# Drivers_-_Low_Current.net
KiCad netlist of a schematic drawn in Altium Designer
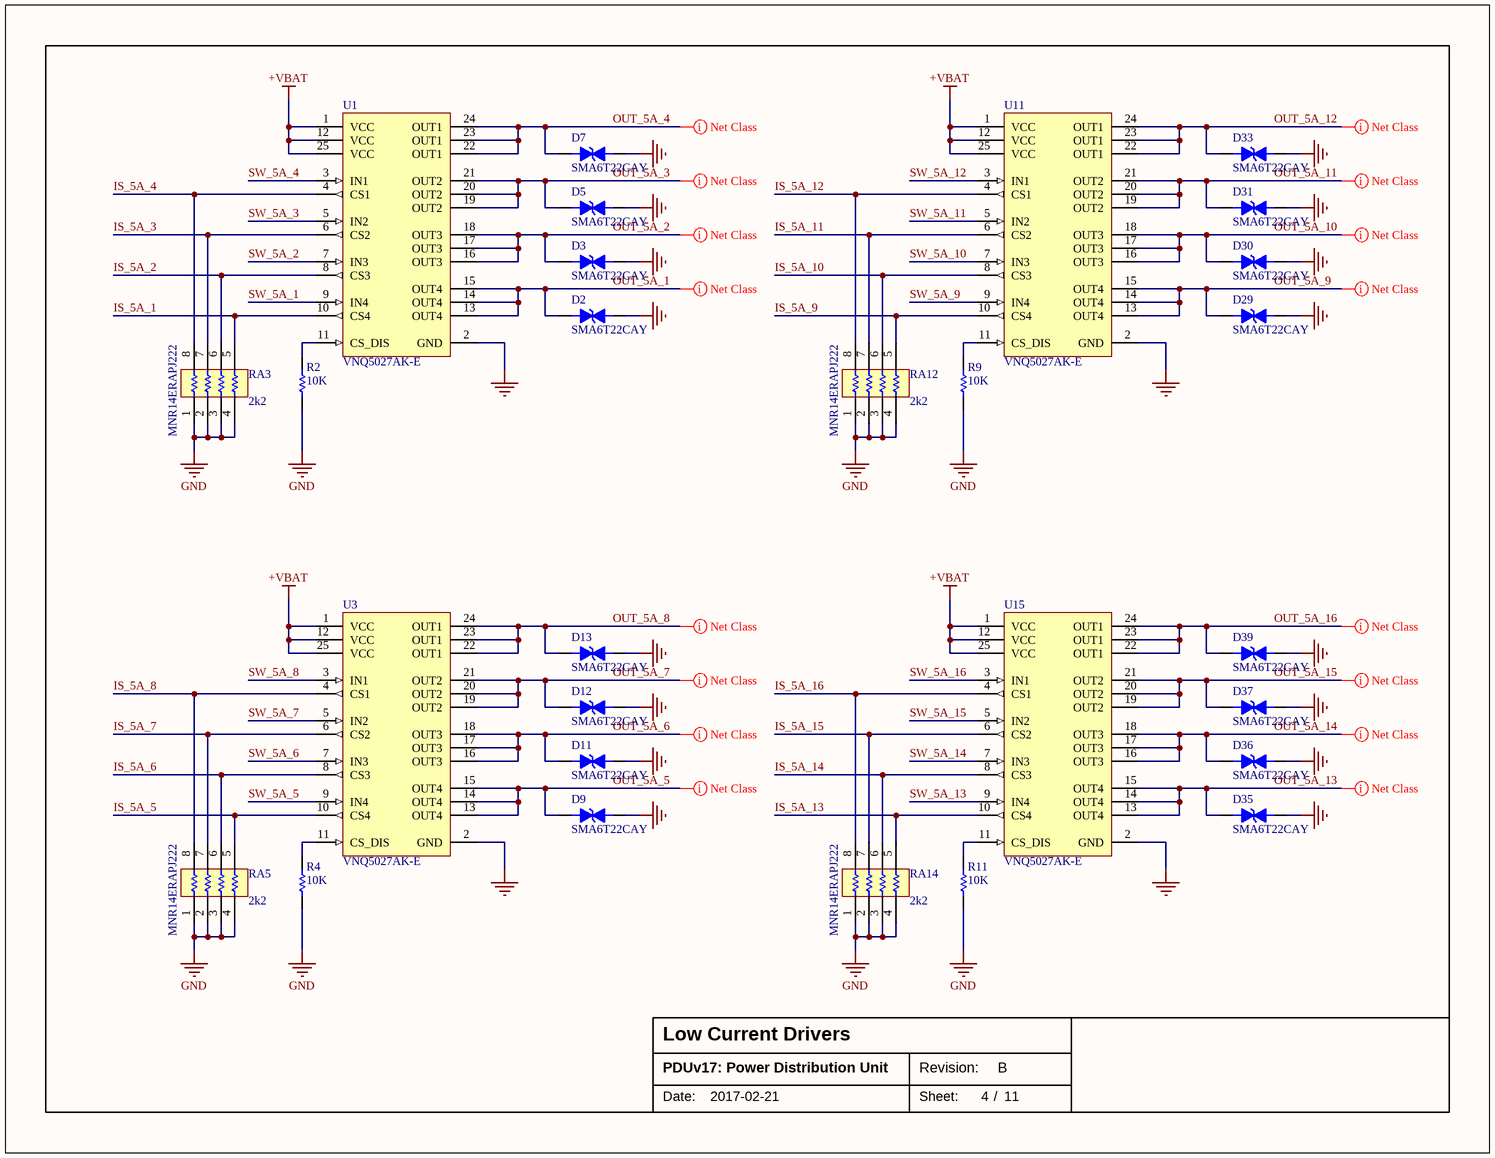
[diagram p0: Drivers - Low Current.SchDoc]

(export (version "E")
  (design (tool "Eeschema 10.0.6"))
  (components
    (comp (ref "D2")
      (value "SMA6T22CAY")
      (footprint "DIOM4326X25N")
      (libsource (lib "PDU-UV17") (part "SMA6T22CAY"))
    )
    (comp (ref "D3")
      (value "SMA6T22CAY")
      (footprint "DIOM4326X25N")
      (libsource (lib "PDU-UV17") (part "SMA6T22CAY"))
    )
    (comp (ref "D5")
      (value "SMA6T22CAY")
      (footprint "DIOM4326X25N")
      (libsource (lib "PDU-UV17") (part "SMA6T22CAY"))
    )
    (comp (ref "D7")
      (value "SMA6T22CAY")
      (footprint "DIOM4326X25N")
      (libsource (lib "PDU-UV17") (part "SMA6T22CAY"))
    )
    (comp (ref "D9")
      (value "SMA6T22CAY")
      (footprint "DIOM4326X25N")
      (libsource (lib "PDU-UV17") (part "SMA6T22CAY"))
    )
    (comp (ref "D11")
      (value "SMA6T22CAY")
      (footprint "DIOM4326X25N")
      (libsource (lib "PDU-UV17") (part "SMA6T22CAY"))
    )
    (comp (ref "D12")
      (value "SMA6T22CAY")
      (footprint "DIOM4326X25N")
      (libsource (lib "PDU-UV17") (part "SMA6T22CAY"))
    )
    (comp (ref "D13")
      (value "SMA6T22CAY")
      (footprint "DIOM4326X25N")
      (libsource (lib "PDU-UV17") (part "SMA6T22CAY"))
    )
    (comp (ref "D29")
      (value "SMA6T22CAY")
      (footprint "DIOM4326X25N")
      (libsource (lib "PDU-UV17") (part "SMA6T22CAY"))
    )
    (comp (ref "D30")
      (value "SMA6T22CAY")
      (footprint "DIOM4326X25N")
      (libsource (lib "PDU-UV17") (part "SMA6T22CAY"))
    )
    (comp (ref "D31")
      (value "SMA6T22CAY")
      (footprint "DIOM4326X25N")
      (libsource (lib "PDU-UV17") (part "SMA6T22CAY"))
    )
    (comp (ref "D33")
      (value "SMA6T22CAY")
      (footprint "DIOM4326X25N")
      (libsource (lib "PDU-UV17") (part "SMA6T22CAY"))
    )
    (comp (ref "D35")
      (value "SMA6T22CAY")
      (footprint "DIOM4326X25N")
      (libsource (lib "PDU-UV17") (part "SMA6T22CAY"))
    )
    (comp (ref "D36")
      (value "SMA6T22CAY")
      (footprint "DIOM4326X25N")
      (libsource (lib "PDU-UV17") (part "SMA6T22CAY"))
    )
    (comp (ref "D37")
      (value "SMA6T22CAY")
      (footprint "DIOM4326X25N")
      (libsource (lib "PDU-UV17") (part "SMA6T22CAY"))
    )
    (comp (ref "D39")
      (value "SMA6T22CAY")
      (footprint "DIOM4326X25N")
      (libsource (lib "PDU-UV17") (part "SMA6T22CAY"))
    )
    (comp (ref "R2")
      (value "10K")
      (footprint "RES-0603-M")
      (fields
        (field (name "PART NUMBER") "RC0603FR-0710KL")
        (field (name "TOLERANCE") "1%")
        (field (name "POWER") "1/10 W")
      )
      (libsource (lib "Resistors") (part "Resistor"))
    )
    (comp (ref "R4")
      (value "10K")
      (footprint "RES-0603-M")
      (fields
        (field (name "PART NUMBER") "RC0603FR-0710KL")
        (field (name "TOLERANCE") "1%")
        (field (name "POWER") "1/10 W")
      )
      (libsource (lib "Resistors") (part "Resistor"))
    )
    (comp (ref "R9")
      (value "10K")
      (footprint "RES-0603-M")
      (fields
        (field (name "PART NUMBER") "RC0603FR-0710KL")
        (field (name "TOLERANCE") "1%")
        (field (name "POWER") "1/10 W")
      )
      (libsource (lib "Resistors") (part "Resistor"))
    )
    (comp (ref "R11")
      (value "10K")
      (footprint "RES-0603-M")
      (fields
        (field (name "PART NUMBER") "RC0603FR-0710KL")
        (field (name "TOLERANCE") "1%")
        (field (name "POWER") "1/10 W")
      )
      (libsource (lib "Resistors") (part "Resistor"))
    )
    (comp (ref "RA3")
      (value "MNR14ERAPJ222")
      (footprint "CAC-80P319X150-8N")
      (fields (field (name "ALTIUM_VALUE") "2k2"))
      (libsource (lib "PDU-UV17") (part "MNR14ERAPJ222"))
    )
    (comp (ref "RA5")
      (value "MNR14ERAPJ222")
      (footprint "CAC-80P319X150-8N")
      (fields (field (name "ALTIUM_VALUE") "2k2"))
      (libsource (lib "PDU-UV17") (part "MNR14ERAPJ222"))
    )
    (comp (ref "RA12")
      (value "MNR14ERAPJ222")
      (footprint "CAC-80P319X150-8N")
      (fields (field (name "ALTIUM_VALUE") "2k2"))
      (libsource (lib "PDU-UV17") (part "MNR14ERAPJ222"))
    )
    (comp (ref "RA14")
      (value "MNR14ERAPJ222")
      (footprint "CAC-80P319X150-8N")
      (fields (field (name "ALTIUM_VALUE") "2k2"))
      (libsource (lib "PDU-UV17") (part "MNR14ERAPJ222"))
    )
    (comp (ref "U1")
      (value "VNQ5027AK-E")
      (footprint "SOP80P1030X245_HS-25N")
      (libsource (lib "PDU-UV17") (part "VNQ5027AK-E"))
    )
    (comp (ref "U3")
      (value "VNQ5027AK-E")
      (footprint "SOP80P1030X245_HS-25N")
      (libsource (lib "PDU-UV17") (part "VNQ5027AK-E"))
    )
    (comp (ref "U11")
      (value "VNQ5027AK-E")
      (footprint "SOP80P1030X245_HS-25N")
      (libsource (lib "PDU-UV17") (part "VNQ5027AK-E"))
    )
    (comp (ref "U15")
      (value "VNQ5027AK-E")
      (footprint "SOP80P1030X245_HS-25N")
      (libsource (lib "PDU-UV17") (part "VNQ5027AK-E"))
    )
  )
  (nets
    (net (code "1") (name "+VBAT") (class "Default")
      (node (ref "U1") (pin "1") (pinfunction "VCC_1") (pintype "power_in"))
      (node (ref "U1") (pin "12") (pinfunction "VCC_12") (pintype "power_in"))
      (node (ref "U1") (pin "25") (pinfunction "VCC_25") (pintype "power_in"))
      (node (ref "U11") (pin "1") (pinfunction "VCC_1") (pintype "power_in"))
      (node (ref "U11") (pin "12") (pinfunction "VCC_12") (pintype "power_in"))
      (node (ref "U11") (pin "25") (pinfunction "VCC_25") (pintype "power_in"))
      (node (ref "U15") (pin "1") (pinfunction "VCC_1") (pintype "power_in"))
      (node (ref "U15") (pin "12") (pinfunction "VCC_12") (pintype "power_in"))
      (node (ref "U15") (pin "25") (pinfunction "VCC_25") (pintype "power_in"))
      (node (ref "U3") (pin "1") (pinfunction "VCC_1") (pintype "power_in"))
      (node (ref "U3") (pin "12") (pinfunction "VCC_12") (pintype "power_in"))
      (node (ref "U3") (pin "25") (pinfunction "VCC_25") (pintype "power_in"))
    )
    (net (code "2") (name "/IS_5A_1") (class "Default")
      (node (ref "RA3") (pin "5") (pinfunction "5_5") (pintype "passive"))
      (node (ref "U1") (pin "10") (pinfunction "CS4_10") (pintype "output"))
    )
    (net (code "3") (name "/IS_5A_2") (class "Default")
      (node (ref "RA3") (pin "6") (pinfunction "6_6") (pintype "passive"))
      (node (ref "U1") (pin "8") (pinfunction "CS3_8") (pintype "output"))
    )
    (net (code "4") (name "/IS_5A_3") (class "Default")
      (node (ref "RA3") (pin "7") (pinfunction "7_7") (pintype "passive"))
      (node (ref "U1") (pin "6") (pinfunction "CS2_6") (pintype "output"))
    )
    (net (code "5") (name "/IS_5A_4") (class "Default")
      (node (ref "RA3") (pin "8") (pinfunction "8_8") (pintype "passive"))
      (node (ref "U1") (pin "4") (pinfunction "CS1_4") (pintype "output"))
    )
    (net (code "6") (name "/IS_5A_5") (class "Default")
      (node (ref "RA5") (pin "5") (pinfunction "5_5") (pintype "passive"))
      (node (ref "U3") (pin "10") (pinfunction "CS4_10") (pintype "output"))
    )
    (net (code "7") (name "/IS_5A_6") (class "Default")
      (node (ref "RA5") (pin "6") (pinfunction "6_6") (pintype "passive"))
      (node (ref "U3") (pin "8") (pinfunction "CS3_8") (pintype "output"))
    )
    (net (code "8") (name "/IS_5A_7") (class "Default")
      (node (ref "RA5") (pin "7") (pinfunction "7_7") (pintype "passive"))
      (node (ref "U3") (pin "6") (pinfunction "CS2_6") (pintype "output"))
    )
    (net (code "9") (name "/IS_5A_8") (class "Default")
      (node (ref "RA5") (pin "8") (pinfunction "8_8") (pintype "passive"))
      (node (ref "U3") (pin "4") (pinfunction "CS1_4") (pintype "output"))
    )
    (net (code "10") (name "/IS_5A_9") (class "Default")
      (node (ref "RA12") (pin "5") (pinfunction "5_5") (pintype "passive"))
      (node (ref "U11") (pin "10") (pinfunction "CS4_10") (pintype "output"))
    )
    (net (code "11") (name "/IS_5A_10") (class "Default")
      (node (ref "RA12") (pin "6") (pinfunction "6_6") (pintype "passive"))
      (node (ref "U11") (pin "8") (pinfunction "CS3_8") (pintype "output"))
    )
    (net (code "12") (name "/IS_5A_11") (class "Default")
      (node (ref "RA12") (pin "7") (pinfunction "7_7") (pintype "passive"))
      (node (ref "U11") (pin "6") (pinfunction "CS2_6") (pintype "output"))
    )
    (net (code "13") (name "/IS_5A_12") (class "Default")
      (node (ref "RA12") (pin "8") (pinfunction "8_8") (pintype "passive"))
      (node (ref "U11") (pin "4") (pinfunction "CS1_4") (pintype "output"))
    )
    (net (code "14") (name "/IS_5A_13") (class "Default")
      (node (ref "RA14") (pin "5") (pinfunction "5_5") (pintype "passive"))
      (node (ref "U15") (pin "10") (pinfunction "CS4_10") (pintype "output"))
    )
    (net (code "15") (name "/IS_5A_14") (class "Default")
      (node (ref "RA14") (pin "6") (pinfunction "6_6") (pintype "passive"))
      (node (ref "U15") (pin "8") (pinfunction "CS3_8") (pintype "output"))
    )
    (net (code "16") (name "/IS_5A_15") (class "Default")
      (node (ref "RA14") (pin "7") (pinfunction "7_7") (pintype "passive"))
      (node (ref "U15") (pin "6") (pinfunction "CS2_6") (pintype "output"))
    )
    (net (code "17") (name "/IS_5A_16") (class "Default")
      (node (ref "RA14") (pin "8") (pinfunction "8_8") (pintype "passive"))
      (node (ref "U15") (pin "4") (pinfunction "CS1_4") (pintype "output"))
    )
    (net (code "18") (name "/OUT_5A_1") (class "Default")
      (node (ref "D2") (pin "2") (pinfunction "A_2") (pintype "passive"))
      (node (ref "U1") (pin "13") (pinfunction "OUT4_13") (pintype "power_in"))
      (node (ref "U1") (pin "14") (pinfunction "OUT4_14") (pintype "power_in"))
      (node (ref "U1") (pin "15") (pinfunction "OUT4_15") (pintype "power_in"))
    )
    (net (code "19") (name "/OUT_5A_2") (class "Default")
      (node (ref "D3") (pin "2") (pinfunction "A_2") (pintype "passive"))
      (node (ref "U1") (pin "16") (pinfunction "OUT3_16") (pintype "power_in"))
      (node (ref "U1") (pin "17") (pinfunction "OUT3_17") (pintype "power_in"))
      (node (ref "U1") (pin "18") (pinfunction "OUT3_18") (pintype "power_in"))
    )
    (net (code "20") (name "/OUT_5A_3") (class "Default")
      (node (ref "D5") (pin "2") (pinfunction "A_2") (pintype "passive"))
      (node (ref "U1") (pin "19") (pinfunction "OUT2_19") (pintype "power_in"))
      (node (ref "U1") (pin "20") (pinfunction "OUT2_20") (pintype "power_in"))
      (node (ref "U1") (pin "21") (pinfunction "OUT2_21") (pintype "power_in"))
    )
    (net (code "21") (name "/OUT_5A_4") (class "Default")
      (node (ref "D7") (pin "2") (pinfunction "A_2") (pintype "passive"))
      (node (ref "U1") (pin "22") (pinfunction "OUT1_22") (pintype "power_in"))
      (node (ref "U1") (pin "23") (pinfunction "OUT1_23") (pintype "power_in"))
      (node (ref "U1") (pin "24") (pinfunction "OUT1_24") (pintype "power_in"))
    )
    (net (code "22") (name "/OUT_5A_5") (class "Default")
      (node (ref "D9") (pin "2") (pinfunction "A_2") (pintype "passive"))
      (node (ref "U3") (pin "13") (pinfunction "OUT4_13") (pintype "power_in"))
      (node (ref "U3") (pin "14") (pinfunction "OUT4_14") (pintype "power_in"))
      (node (ref "U3") (pin "15") (pinfunction "OUT4_15") (pintype "power_in"))
    )
    (net (code "23") (name "/OUT_5A_6") (class "Default")
      (node (ref "D11") (pin "2") (pinfunction "A_2") (pintype "passive"))
      (node (ref "U3") (pin "16") (pinfunction "OUT3_16") (pintype "power_in"))
      (node (ref "U3") (pin "17") (pinfunction "OUT3_17") (pintype "power_in"))
      (node (ref "U3") (pin "18") (pinfunction "OUT3_18") (pintype "power_in"))
    )
    (net (code "24") (name "/OUT_5A_7") (class "Default")
      (node (ref "D12") (pin "2") (pinfunction "A_2") (pintype "passive"))
      (node (ref "U3") (pin "19") (pinfunction "OUT2_19") (pintype "power_in"))
      (node (ref "U3") (pin "20") (pinfunction "OUT2_20") (pintype "power_in"))
      (node (ref "U3") (pin "21") (pinfunction "OUT2_21") (pintype "power_in"))
    )
    (net (code "25") (name "/OUT_5A_8") (class "Default")
      (node (ref "D13") (pin "2") (pinfunction "A_2") (pintype "passive"))
      (node (ref "U3") (pin "22") (pinfunction "OUT1_22") (pintype "power_in"))
      (node (ref "U3") (pin "23") (pinfunction "OUT1_23") (pintype "power_in"))
      (node (ref "U3") (pin "24") (pinfunction "OUT1_24") (pintype "power_in"))
    )
    (net (code "26") (name "/OUT_5A_9") (class "Default")
      (node (ref "D29") (pin "2") (pinfunction "A_2") (pintype "passive"))
      (node (ref "U11") (pin "13") (pinfunction "OUT4_13") (pintype "power_in"))
      (node (ref "U11") (pin "14") (pinfunction "OUT4_14") (pintype "power_in"))
      (node (ref "U11") (pin "15") (pinfunction "OUT4_15") (pintype "power_in"))
    )
    (net (code "27") (name "/OUT_5A_10") (class "Default")
      (node (ref "D30") (pin "2") (pinfunction "A_2") (pintype "passive"))
      (node (ref "U11") (pin "16") (pinfunction "OUT3_16") (pintype "power_in"))
      (node (ref "U11") (pin "17") (pinfunction "OUT3_17") (pintype "power_in"))
      (node (ref "U11") (pin "18") (pinfunction "OUT3_18") (pintype "power_in"))
    )
    (net (code "28") (name "/OUT_5A_11") (class "Default")
      (node (ref "D31") (pin "2") (pinfunction "A_2") (pintype "passive"))
      (node (ref "U11") (pin "19") (pinfunction "OUT2_19") (pintype "power_in"))
      (node (ref "U11") (pin "20") (pinfunction "OUT2_20") (pintype "power_in"))
      (node (ref "U11") (pin "21") (pinfunction "OUT2_21") (pintype "power_in"))
    )
    (net (code "29") (name "/OUT_5A_12") (class "Default")
      (node (ref "D33") (pin "2") (pinfunction "A_2") (pintype "passive"))
      (node (ref "U11") (pin "22") (pinfunction "OUT1_22") (pintype "power_in"))
      (node (ref "U11") (pin "23") (pinfunction "OUT1_23") (pintype "power_in"))
      (node (ref "U11") (pin "24") (pinfunction "OUT1_24") (pintype "power_in"))
    )
    (net (code "30") (name "/OUT_5A_13") (class "Default")
      (node (ref "D35") (pin "2") (pinfunction "A_2") (pintype "passive"))
      (node (ref "U15") (pin "13") (pinfunction "OUT4_13") (pintype "power_in"))
      (node (ref "U15") (pin "14") (pinfunction "OUT4_14") (pintype "power_in"))
      (node (ref "U15") (pin "15") (pinfunction "OUT4_15") (pintype "power_in"))
    )
    (net (code "31") (name "/OUT_5A_14") (class "Default")
      (node (ref "D36") (pin "2") (pinfunction "A_2") (pintype "passive"))
      (node (ref "U15") (pin "16") (pinfunction "OUT3_16") (pintype "power_in"))
      (node (ref "U15") (pin "17") (pinfunction "OUT3_17") (pintype "power_in"))
      (node (ref "U15") (pin "18") (pinfunction "OUT3_18") (pintype "power_in"))
    )
    (net (code "32") (name "/OUT_5A_15") (class "Default")
      (node (ref "D37") (pin "2") (pinfunction "A_2") (pintype "passive"))
      (node (ref "U15") (pin "19") (pinfunction "OUT2_19") (pintype "power_in"))
      (node (ref "U15") (pin "20") (pinfunction "OUT2_20") (pintype "power_in"))
      (node (ref "U15") (pin "21") (pinfunction "OUT2_21") (pintype "power_in"))
    )
    (net (code "33") (name "/OUT_5A_16") (class "Default")
      (node (ref "D39") (pin "2") (pinfunction "A_2") (pintype "passive"))
      (node (ref "U15") (pin "22") (pinfunction "OUT1_22") (pintype "power_in"))
      (node (ref "U15") (pin "23") (pinfunction "OUT1_23") (pintype "power_in"))
      (node (ref "U15") (pin "24") (pinfunction "OUT1_24") (pintype "power_in"))
    )
    (net (code "34") (name "/SW_5A_1") (class "Default")
      (node (ref "U1") (pin "9") (pinfunction "IN4_9") (pintype "input"))
    )
    (net (code "35") (name "/SW_5A_2") (class "Default")
      (node (ref "U1") (pin "7") (pinfunction "IN3_7") (pintype "input"))
    )
    (net (code "36") (name "/SW_5A_3") (class "Default")
      (node (ref "U1") (pin "5") (pinfunction "IN2_5") (pintype "input"))
    )
    (net (code "37") (name "/SW_5A_4") (class "Default")
      (node (ref "U1") (pin "3") (pinfunction "IN1_3") (pintype "input"))
    )
    (net (code "38") (name "/SW_5A_5") (class "Default")
      (node (ref "U3") (pin "9") (pinfunction "IN4_9") (pintype "input"))
    )
    (net (code "39") (name "/SW_5A_6") (class "Default")
      (node (ref "U3") (pin "7") (pinfunction "IN3_7") (pintype "input"))
    )
    (net (code "40") (name "/SW_5A_7") (class "Default")
      (node (ref "U3") (pin "5") (pinfunction "IN2_5") (pintype "input"))
    )
    (net (code "41") (name "/SW_5A_8") (class "Default")
      (node (ref "U3") (pin "3") (pinfunction "IN1_3") (pintype "input"))
    )
    (net (code "42") (name "/SW_5A_9") (class "Default")
      (node (ref "U11") (pin "9") (pinfunction "IN4_9") (pintype "input"))
    )
    (net (code "43") (name "/SW_5A_10") (class "Default")
      (node (ref "U11") (pin "7") (pinfunction "IN3_7") (pintype "input"))
    )
    (net (code "44") (name "/SW_5A_11") (class "Default")
      (node (ref "U11") (pin "5") (pinfunction "IN2_5") (pintype "input"))
    )
    (net (code "45") (name "/SW_5A_12") (class "Default")
      (node (ref "U11") (pin "3") (pinfunction "IN1_3") (pintype "input"))
    )
    (net (code "46") (name "/SW_5A_13") (class "Default")
      (node (ref "U15") (pin "9") (pinfunction "IN4_9") (pintype "input"))
    )
    (net (code "47") (name "/SW_5A_14") (class "Default")
      (node (ref "U15") (pin "7") (pinfunction "IN3_7") (pintype "input"))
    )
    (net (code "48") (name "/SW_5A_15") (class "Default")
      (node (ref "U15") (pin "5") (pinfunction "IN2_5") (pintype "input"))
    )
    (net (code "49") (name "/SW_5A_16") (class "Default")
      (node (ref "U15") (pin "3") (pinfunction "IN1_3") (pintype "input"))
    )
    (net (code "50") (name "GND") (class "Default")
      (node (ref "D11") (pin "1") (pinfunction "K_1") (pintype "passive"))
      (node (ref "D12") (pin "1") (pinfunction "K_1") (pintype "passive"))
      (node (ref "D13") (pin "1") (pinfunction "K_1") (pintype "passive"))
      (node (ref "D2") (pin "1") (pinfunction "K_1") (pintype "passive"))
      (node (ref "D29") (pin "1") (pinfunction "K_1") (pintype "passive"))
      (node (ref "D3") (pin "1") (pinfunction "K_1") (pintype "passive"))
      (node (ref "D30") (pin "1") (pinfunction "K_1") (pintype "passive"))
      (node (ref "D31") (pin "1") (pinfunction "K_1") (pintype "passive"))
      (node (ref "D33") (pin "1") (pinfunction "K_1") (pintype "passive"))
      (node (ref "D35") (pin "1") (pinfunction "K_1") (pintype "passive"))
      (node (ref "D36") (pin "1") (pinfunction "K_1") (pintype "passive"))
      (node (ref "D37") (pin "1") (pinfunction "K_1") (pintype "passive"))
      (node (ref "D39") (pin "1") (pinfunction "K_1") (pintype "passive"))
      (node (ref "D5") (pin "1") (pinfunction "K_1") (pintype "passive"))
      (node (ref "D7") (pin "1") (pinfunction "K_1") (pintype "passive"))
      (node (ref "D9") (pin "1") (pinfunction "K_1") (pintype "passive"))
      (node (ref "R11") (pin "1") (pinfunction "1_1") (pintype "passive"))
      (node (ref "R2") (pin "1") (pinfunction "1_1") (pintype "passive"))
      (node (ref "R4") (pin "1") (pinfunction "1_1") (pintype "passive"))
      (node (ref "R9") (pin "1") (pinfunction "1_1") (pintype "passive"))
      (node (ref "RA12") (pin "1") (pinfunction "1_1") (pintype "passive"))
      (node (ref "RA12") (pin "2") (pinfunction "2_2") (pintype "passive"))
      (node (ref "RA12") (pin "3") (pinfunction "3_3") (pintype "passive"))
      (node (ref "RA12") (pin "4") (pinfunction "4_4") (pintype "passive"))
      (node (ref "RA14") (pin "1") (pinfunction "1_1") (pintype "passive"))
      (node (ref "RA14") (pin "2") (pinfunction "2_2") (pintype "passive"))
      (node (ref "RA14") (pin "3") (pinfunction "3_3") (pintype "passive"))
      (node (ref "RA14") (pin "4") (pinfunction "4_4") (pintype "passive"))
      (node (ref "RA3") (pin "1") (pinfunction "1_1") (pintype "passive"))
      (node (ref "RA3") (pin "2") (pinfunction "2_2") (pintype "passive"))
      (node (ref "RA3") (pin "3") (pinfunction "3_3") (pintype "passive"))
      (node (ref "RA3") (pin "4") (pinfunction "4_4") (pintype "passive"))
      (node (ref "RA5") (pin "1") (pinfunction "1_1") (pintype "passive"))
      (node (ref "RA5") (pin "2") (pinfunction "2_2") (pintype "passive"))
      (node (ref "RA5") (pin "3") (pinfunction "3_3") (pintype "passive"))
      (node (ref "RA5") (pin "4") (pinfunction "4_4") (pintype "passive"))
      (node (ref "U1") (pin "2") (pinfunction "GND_2") (pintype "power_in"))
      (node (ref "U11") (pin "2") (pinfunction "GND_2") (pintype "power_in"))
      (node (ref "U15") (pin "2") (pinfunction "GND_2") (pintype "power_in"))
      (node (ref "U3") (pin "2") (pinfunction "GND_2") (pintype "power_in"))
    )
    (net (code "51") (name "Net-(U1-CS_DIS)") (class "Default")
      (node (ref "R2") (pin "2") (pinfunction "2_2") (pintype "passive"))
      (node (ref "U1") (pin "11") (pinfunction "CS_DIS_11") (pintype "input"))
    )
    (net (code "52") (name "Net-(U3-CS_DIS)") (class "Default")
      (node (ref "R4") (pin "2") (pinfunction "2_2") (pintype "passive"))
      (node (ref "U3") (pin "11") (pinfunction "CS_DIS_11") (pintype "input"))
    )
    (net (code "53") (name "Net-(U11-CS_DIS)") (class "Default")
      (node (ref "R9") (pin "2") (pinfunction "2_2") (pintype "passive"))
      (node (ref "U11") (pin "11") (pinfunction "CS_DIS_11") (pintype "input"))
    )
    (net (code "54") (name "Net-(U15-CS_DIS)") (class "Default")
      (node (ref "R11") (pin "2") (pinfunction "2_2") (pintype "passive"))
      (node (ref "U15") (pin "11") (pinfunction "CS_DIS_11") (pintype "input"))
    )
  )
)
